# WiFi.net
KiCad netlist of a schematic drawn in Altium Designer
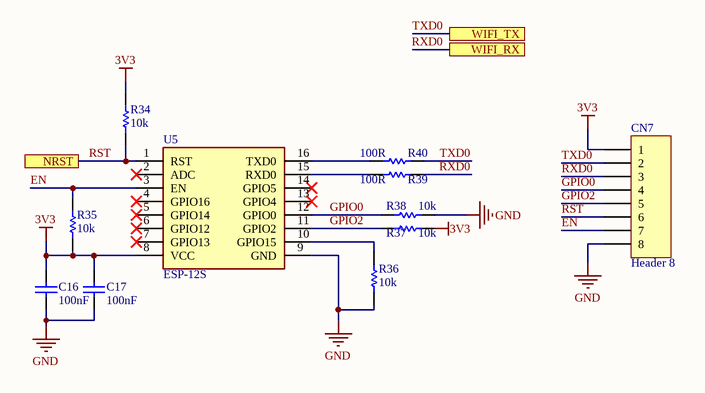
[diagram p0: WiFi.SchDoc]

(export (version "E")
  (design (tool "Eeschema 10.0.6"))
  (components
    (comp (ref "C16")
      (value "100nF")
      (footprint "1608[0603]")
      (description "Capacitor")
      (fields (field (name "Comment") "Cap") (field (name "PUBLISHER") "Altium Limited"))
      (libsource (lib "Miscellaneous Devices") (part "Cap"))
    )
    (comp (ref "C17")
      (value "100nF")
      (footprint "1608[0603]")
      (description "Capacitor")
      (fields (field (name "Comment") "Cap") (field (name "PUBLISHER") "Altium Limited"))
      (libsource (lib "Miscellaneous Devices") (part "Cap"))
    )
    (comp (ref "CN7")
      (value "Header 8")
      (footprint "HDR1X8")
      (description "Header, 8-Pin")
      (fields (field (name "PUBLISHER") "Altium Limited"))
      (libsource (lib "Miscellaneous Connectors") (part "Header 8"))
    )
    (comp (ref "R34")
      (value "10k")
      (footprint "1608[0603]")
      (description "Resistor")
      (fields (field (name "Comment") "Res1") (field (name "PUBLISHER") "Altium Limited"))
      (libsource (lib "Miscellaneous Devices") (part "Res1"))
    )
    (comp (ref "R35")
      (value "10k")
      (footprint "1608[0603]")
      (description "Resistor")
      (fields (field (name "Comment") "Res1") (field (name "PUBLISHER") "Altium Limited"))
      (libsource (lib "Miscellaneous Devices") (part "Res1"))
    )
    (comp (ref "R36")
      (value "10k")
      (footprint "1608[0603]")
      (description "Resistor")
      (fields (field (name "Comment") "Res1") (field (name "PUBLISHER") "Altium Limited"))
      (libsource (lib "Miscellaneous Devices") (part "Res1"))
    )
    (comp (ref "R37")
      (value "10k")
      (footprint "1608[0603]")
      (description "Resistor")
      (fields (field (name "Comment") "Res1") (field (name "PUBLISHER") "Altium Limited"))
      (libsource (lib "Miscellaneous Devices") (part "Res1"))
    )
    (comp (ref "R38")
      (value "10k")
      (footprint "1608[0603]")
      (description "Resistor")
      (fields (field (name "Comment") "Res1") (field (name "PUBLISHER") "Altium Limited"))
      (libsource (lib "Miscellaneous Devices") (part "Res1"))
    )
    (comp (ref "R39")
      (value "100R")
      (footprint "1608[0603]")
      (description "Resistor")
      (fields (field (name "Comment") "Res1") (field (name "PUBLISHER") "Altium Limited"))
      (libsource (lib "Miscellaneous Devices") (part "Res1"))
    )
    (comp (ref "R40")
      (value "100R")
      (footprint "1608[0603]")
      (description "Resistor")
      (fields (field (name "Comment") "Res1") (field (name "PUBLISHER") "Altium Limited"))
      (libsource (lib "Miscellaneous Devices") (part "Res1"))
    )
    (comp (ref "U5")
      (value "ESP-12S")
      (footprint "SamacSys:ESP12S")
      (description "Integrated Circuit")
      (fields (field (name "MOUSER PART NUMBER") "223-ESP-12S"))
      (libsource (lib "*") (part "ESP-12S"))
    )
  )
  (nets
    (net (code "1") (name "/EN") (class "Default")
      (node (ref "CN7") (pin "7") (pinfunction "7_7") (pintype "passive"))
      (node (ref "R35") (pin "1") (pinfunction "1_1") (pintype "passive"))
      (node (ref "U5") (pin "3") (pinfunction "EN_3") (pintype "passive"))
    )
    (net (code "2") (name "/GPIO0") (class "Default")
      (node (ref "CN7") (pin "4") (pinfunction "4_4") (pintype "passive"))
      (node (ref "R38") (pin "1") (pinfunction "1_1") (pintype "passive"))
      (node (ref "U5") (pin "12") (pinfunction "GPIO0_12") (pintype "passive"))
    )
    (net (code "3") (name "/GPIO2") (class "Default")
      (node (ref "CN7") (pin "5") (pinfunction "5_5") (pintype "passive"))
      (node (ref "R37") (pin "1") (pinfunction "1_1") (pintype "passive"))
      (node (ref "U5") (pin "11") (pinfunction "GPIO2_11") (pintype "passive"))
    )
    (net (code "4") (name "/RST") (class "Default")
      (node (ref "CN7") (pin "6") (pinfunction "6_6") (pintype "passive"))
      (node (ref "R34") (pin "1") (pinfunction "1_1") (pintype "passive"))
      (node (ref "U5") (pin "1") (pinfunction "RST_1") (pintype "passive"))
    )
    (net (code "5") (name "/RXD0") (class "Default")
      (node (ref "CN7") (pin "3") (pinfunction "3_3") (pintype "passive"))
      (node (ref "R39") (pin "1") (pinfunction "1_1") (pintype "passive"))
    )
    (net (code "6") (name "/TXD0") (class "Default")
      (node (ref "CN7") (pin "2") (pinfunction "2_2") (pintype "passive"))
      (node (ref "R40") (pin "1") (pinfunction "1_1") (pintype "passive"))
    )
    (net (code "7") (name "3V3") (class "Default")
      (node (ref "C16") (pin "1") (pinfunction "1_1") (pintype "passive"))
      (node (ref "C17") (pin "1") (pinfunction "1_1") (pintype "passive"))
      (node (ref "CN7") (pin "1") (pinfunction "1_1") (pintype "passive"))
      (node (ref "R34") (pin "2") (pinfunction "2_2") (pintype "passive"))
      (node (ref "R35") (pin "2") (pinfunction "2_2") (pintype "passive"))
      (node (ref "R37") (pin "2") (pinfunction "2_2") (pintype "passive"))
      (node (ref "U5") (pin "8") (pinfunction "VCC_8") (pintype "passive"))
    )
    (net (code "8") (name "GND") (class "Default")
      (node (ref "C16") (pin "2") (pinfunction "2_2") (pintype "passive"))
      (node (ref "C17") (pin "2") (pinfunction "2_2") (pintype "passive"))
      (node (ref "CN7") (pin "8") (pinfunction "8_8") (pintype "passive"))
      (node (ref "R36") (pin "2") (pinfunction "2_2") (pintype "passive"))
      (node (ref "R38") (pin "2") (pinfunction "2_2") (pintype "passive"))
      (node (ref "U5") (pin "9") (pinfunction "GND_9") (pintype "passive"))
    )
    (net (code "9") (name "Net-(U5-GPIO15)") (class "Default")
      (node (ref "R36") (pin "1") (pinfunction "1_1") (pintype "passive"))
      (node (ref "U5") (pin "10") (pinfunction "GPIO15_10") (pintype "passive"))
    )
    (net (code "10") (name "Net-(U5-RXD0)") (class "Default")
      (node (ref "R39") (pin "2") (pinfunction "2_2") (pintype "passive"))
      (node (ref "U5") (pin "15") (pinfunction "RXD0_15") (pintype "passive"))
    )
    (net (code "11") (name "Net-(U5-TXD0)") (class "Default")
      (node (ref "R40") (pin "2") (pinfunction "2_2") (pintype "passive"))
      (node (ref "U5") (pin "16") (pinfunction "TXD0_16") (pintype "passive"))
    )
    (net (code "12") (name "unconnected-(U5-ADC-Pad2)") (class "Default")
      (node (ref "U5") (pin "2") (pinfunction "ADC_2") (pintype "passive+no_connect"))
    )
    (net (code "13") (name "unconnected-(U5-GPIO4-Pad13)") (class "Default")
      (node (ref "U5") (pin "13") (pinfunction "GPIO4_13") (pintype "passive+no_connect"))
    )
    (net (code "14") (name "unconnected-(U5-GPIO5-Pad14)") (class "Default")
      (node (ref "U5") (pin "14") (pinfunction "GPIO5_14") (pintype "passive+no_connect"))
    )
    (net (code "15") (name "unconnected-(U5-GPIO12-Pad6)") (class "Default")
      (node (ref "U5") (pin "6") (pinfunction "GPIO12_6") (pintype "passive+no_connect"))
    )
    (net (code "16") (name "unconnected-(U5-GPIO13-Pad7)") (class "Default")
      (node (ref "U5") (pin "7") (pinfunction "GPIO13_7") (pintype "passive+no_connect"))
    )
    (net (code "17") (name "unconnected-(U5-GPIO14-Pad5)") (class "Default")
      (node (ref "U5") (pin "5") (pinfunction "GPIO14_5") (pintype "passive+no_connect"))
    )
    (net (code "18") (name "unconnected-(U5-GPIO16-Pad4)") (class "Default")
      (node (ref "U5") (pin "4") (pinfunction "GPIO16_4") (pintype "passive+no_connect"))
    )
  )
)
